# airu-schematic-bb.net
KiCad netlist of a schematic drawn in EAGLE
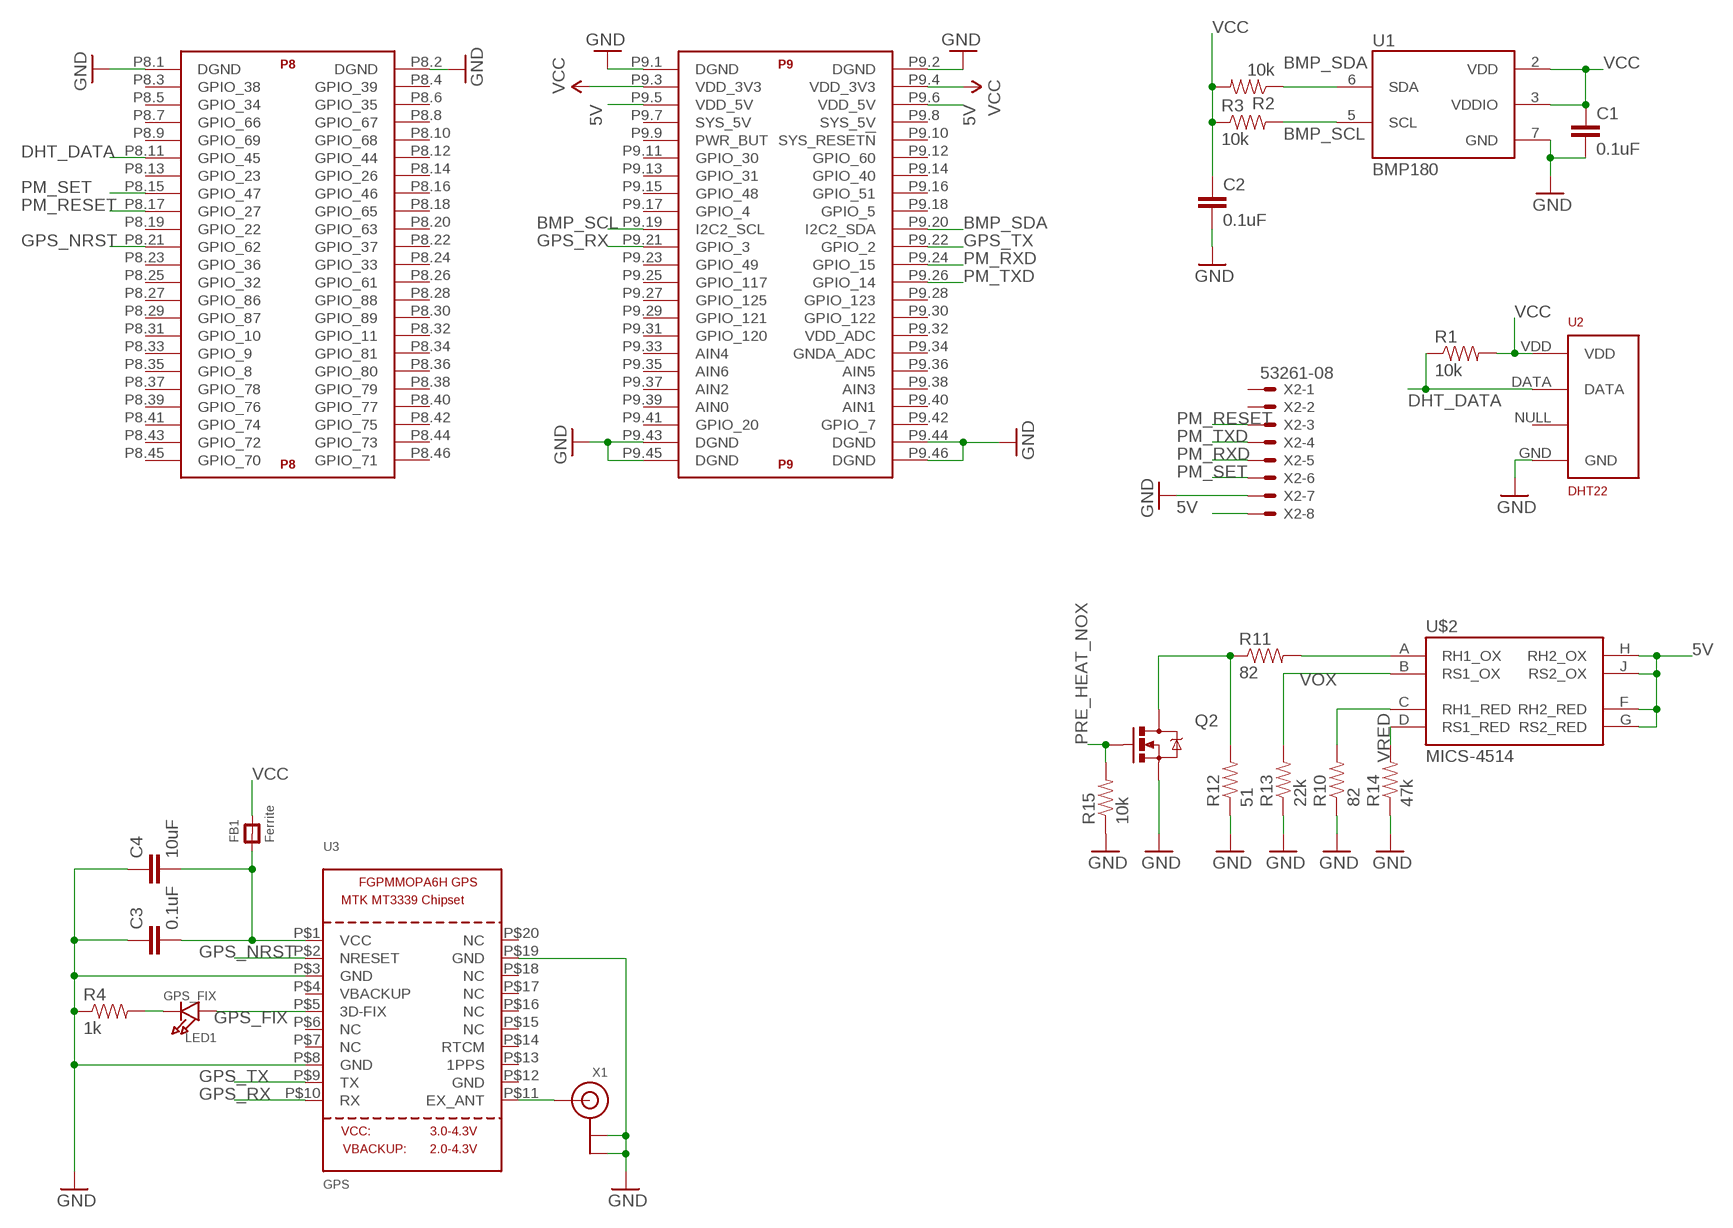
[diagram p0: schematic, sheet 1]

(export (version "E")
  (design (tool "Eeschema 10.0.6"))
  (components
    (comp (ref "C1")
      (value "0.1uF")
      (footprint "eagle-import:1206")
      (libsource (lib "eagle-import") (part "CAP1206"))
    )
    (comp (ref "C2")
      (value "0.1uF")
      (footprint "eagle-import:1206")
      (libsource (lib "eagle-import") (part "CAP1206"))
    )
    (comp (ref "C3")
      (value "0.1uF")
      (footprint "eagle-import:1206")
      (libsource (lib "eagle-import") (part "CAP1206"))
    )
    (comp (ref "C4")
      (value "10uF")
      (footprint "eagle-import:1206")
      (libsource (lib "eagle-import") (part "CAP1206"))
    )
    (comp (ref "FB1")
      (value "Ferrite")
      (footprint "eagle-import:0805")
      (libsource (lib "eagle-import") (part "FERRITE0805"))
    )
    (comp (ref "LED1")
      (value "GPS_FIX")
      (footprint "eagle-import:CHIPLED_1206")
      (libsource (lib "eagle-import") (part "LED1206"))
    )
    (comp (ref "Q2")
      (value "MOSFET-NCHANNELAO3404A")
      (footprint "eagle-import:SOT23-3")
      (libsource (lib "eagle-import") (part "MOSFET-NCHANNELAO3404A"))
    )
    (comp (ref "R1")
      (value "10k")
      (footprint "eagle-import:1206")
      (libsource (lib "eagle-import") (part "RESISTOR1206"))
    )
    (comp (ref "R2")
      (value "10k")
      (footprint "eagle-import:1206")
      (libsource (lib "eagle-import") (part "RESISTOR1206"))
    )
    (comp (ref "R3")
      (value "10k")
      (footprint "eagle-import:1206")
      (libsource (lib "eagle-import") (part "RESISTOR1206"))
    )
    (comp (ref "R4")
      (value "1k")
      (footprint "eagle-import:1206")
      (libsource (lib "eagle-import") (part "RESISTOR1206"))
    )
    (comp (ref "R10")
      (value "82")
      (footprint "eagle-import:1206")
      (libsource (lib "eagle-import") (part "RESISTOR1206"))
    )
    (comp (ref "R11")
      (value "82")
      (footprint "eagle-import:1206")
      (libsource (lib "eagle-import") (part "RESISTOR1206"))
    )
    (comp (ref "R12")
      (value "51")
      (footprint "eagle-import:1206")
      (libsource (lib "eagle-import") (part "RESISTOR1206"))
    )
    (comp (ref "R13")
      (value "22k")
      (footprint "eagle-import:1206")
      (libsource (lib "eagle-import") (part "RESISTOR1206"))
    )
    (comp (ref "R14")
      (value "47k")
      (footprint "eagle-import:1206")
      (libsource (lib "eagle-import") (part "RESISTOR1206"))
    )
    (comp (ref "R15")
      (value "10k")
      (footprint "eagle-import:1206")
      (libsource (lib "eagle-import") (part "RESISTOR1206"))
    )
    (comp (ref "U$1")
      (value "BEAGLE_BONE_BLACK_CAPE")
      (footprint "eagle-import:BEAGLE_BONE_BLACK_CAPE")
      (libsource (lib "eagle-import") (part "BEAGLE_BONE_BLACK_CAPE"))
    )
    (comp (ref "U$2")
      (value "MICS-4514")
      (footprint "eagle-import:MICS_10-SMD")
      (libsource (lib "eagle-import") (part "MICS-4514"))
    )
    (comp (ref "U1")
      (value "BMP180")
      (footprint "eagle-import:BMP180")
      (libsource (lib "eagle-import") (part "BMP180"))
    )
    (comp (ref "U2")
      (value "DHT22")
      (footprint "eagle-import:RHT03_DHT-22")
      (libsource (lib "eagle-import") (part "RHT03_DHT-22_AM2302"))
    )
    (comp (ref "U3")
      (value "GPS")
      (footprint "eagle-import:FGPMMOPA6H")
      (libsource (lib "eagle-import") (part "GPS_FGPMMOPA6H"))
    )
    (comp (ref "X1")
      (value "ANTENNA_U.FL")
      (footprint "eagle-import:U.FL")
      (libsource (lib "eagle-import") (part "ANTENNA_U.FL"))
    )
    (comp (ref "X2")
      (value "53261-08")
      (footprint "eagle-import:53261-08")
      (libsource (lib "eagle-import") (part "53?-08261"))
    )
  )
  (nets
    (net (code "1") (name "/5V") (class "Default")
      (node (ref "U$1") (pin "P9.5") (pinfunction "VDD_5V_P9.5") (pintype "bidirectional"))
      (node (ref "U$1") (pin "P9.6") (pinfunction "VDD_5V_P9.6") (pintype "bidirectional"))
      (node (ref "U$2") (pin "F") (pinfunction "RH2_RED_F") (pintype "bidirectional"))
      (node (ref "U$2") (pin "G") (pinfunction "RS2_RED_G") (pintype "bidirectional"))
      (node (ref "U$2") (pin "H") (pinfunction "RH2_OX_H") (pintype "bidirectional"))
      (node (ref "U$2") (pin "J") (pinfunction "RS2_OX_J") (pintype "bidirectional"))
      (node (ref "X2") (pin "8") (pinfunction "S_8") (pintype "passive"))
    )
    (net (code "2") (name "/BMP_SCL") (class "Default")
      (node (ref "R3") (pin "2") (pinfunction "2_2") (pintype "passive"))
      (node (ref "U$1") (pin "P9.19") (pinfunction "I2C2_SCL_P9.19") (pintype "bidirectional"))
      (node (ref "U1") (pin "5") (pinfunction "SCL_5") (pintype "input"))
    )
    (net (code "3") (name "/BMP_SDA") (class "Default")
      (node (ref "R2") (pin "1") (pinfunction "1_1") (pintype "passive"))
      (node (ref "U$1") (pin "P9.20") (pinfunction "I2C2_SDA_P9.20") (pintype "bidirectional"))
      (node (ref "U1") (pin "6") (pinfunction "SDA_6") (pintype "bidirectional"))
    )
    (net (code "4") (name "/DHT_DATA") (class "Default")
      (node (ref "R1") (pin "1") (pinfunction "1_1") (pintype "passive"))
      (node (ref "U$1") (pin "P8.11") (pinfunction "GPIO_45_P8.11") (pintype "bidirectional"))
      (node (ref "U2") (pin "DATA") (pinfunction "DATA_DATA") (pintype "bidirectional"))
    )
    (net (code "5") (name "/GPS_FIX") (class "Default")
      (node (ref "LED1") (pin "A") (pinfunction "A_A") (pintype "passive"))
      (node (ref "U3") (pin "P$5") (pinfunction "3D-FIX_P$5") (pintype "bidirectional"))
    )
    (net (code "6") (name "/GPS_NRST") (class "Default")
      (node (ref "U$1") (pin "P8.21") (pinfunction "GPIO_62_P8.21") (pintype "bidirectional"))
      (node (ref "U3") (pin "P$2") (pinfunction "NRESET_P$2") (pintype "bidirectional"))
    )
    (net (code "7") (name "/GPS_RX") (class "Default")
      (node (ref "U$1") (pin "P9.21") (pinfunction "GPIO_3_P9.21") (pintype "bidirectional"))
      (node (ref "U3") (pin "P$10") (pinfunction "RX_P$10") (pintype "bidirectional"))
    )
    (net (code "8") (name "/GPS_TX") (class "Default")
      (node (ref "U$1") (pin "P9.22") (pinfunction "GPIO_2_P9.22") (pintype "bidirectional"))
      (node (ref "U3") (pin "P$9") (pinfunction "TX_P$9") (pintype "bidirectional"))
    )
    (net (code "9") (name "/PM_RESET") (class "Default")
      (node (ref "U$1") (pin "P8.17") (pinfunction "GPIO_27_P8.17") (pintype "bidirectional"))
      (node (ref "X2") (pin "3") (pinfunction "S_3") (pintype "passive"))
    )
    (net (code "10") (name "/PM_RXD") (class "Default")
      (node (ref "U$1") (pin "P9.24") (pinfunction "GPIO_15_P9.24") (pintype "bidirectional"))
      (node (ref "X2") (pin "5") (pinfunction "S_5") (pintype "passive"))
    )
    (net (code "11") (name "/PM_SET") (class "Default")
      (node (ref "U$1") (pin "P8.15") (pinfunction "GPIO_47_P8.15") (pintype "bidirectional"))
      (node (ref "X2") (pin "6") (pinfunction "S_6") (pintype "passive"))
    )
    (net (code "12") (name "/PM_TXD") (class "Default")
      (node (ref "U$1") (pin "P9.26") (pinfunction "GPIO_14_P9.26") (pintype "bidirectional"))
      (node (ref "X2") (pin "4") (pinfunction "S_4") (pintype "passive"))
    )
    (net (code "13") (name "/PRE_HEAT_NOX") (class "Default")
      (node (ref "Q2") (pin "1") (pinfunction "G_1") (pintype "passive"))
      (node (ref "R15") (pin "2") (pinfunction "2_2") (pintype "passive"))
    )
    (net (code "14") (name "/VOX") (class "Default")
      (node (ref "R13") (pin "2") (pinfunction "2_2") (pintype "passive"))
      (node (ref "U$2") (pin "B") (pinfunction "RS1_OX_B") (pintype "bidirectional"))
    )
    (net (code "15") (name "/VRED") (class "Default")
      (node (ref "R14") (pin "2") (pinfunction "2_2") (pintype "passive"))
      (node (ref "U$2") (pin "D") (pinfunction "RS1_RED_D") (pintype "bidirectional"))
    )
    (net (code "16") (name "GND") (class "Default")
      (node (ref "C1") (pin "2") (pinfunction "2_2") (pintype "passive"))
      (node (ref "C2") (pin "2") (pinfunction "2_2") (pintype "passive"))
      (node (ref "C3") (pin "1") (pinfunction "1_1") (pintype "passive"))
      (node (ref "C4") (pin "1") (pinfunction "1_1") (pintype "passive"))
      (node (ref "Q2") (pin "2") (pinfunction "S_2") (pintype "passive"))
      (node (ref "R10") (pin "1") (pinfunction "1_1") (pintype "passive"))
      (node (ref "R12") (pin "1") (pinfunction "1_1") (pintype "passive"))
      (node (ref "R13") (pin "1") (pinfunction "1_1") (pintype "passive"))
      (node (ref "R14") (pin "1") (pinfunction "1_1") (pintype "passive"))
      (node (ref "R15") (pin "1") (pinfunction "1_1") (pintype "passive"))
      (node (ref "R4") (pin "1") (pinfunction "1_1") (pintype "passive"))
      (node (ref "U$1") (pin "P8.1") (pinfunction "DGND_P8.1") (pintype "bidirectional"))
      (node (ref "U$1") (pin "P8.2") (pinfunction "DGND_P8.2") (pintype "bidirectional"))
      (node (ref "U$1") (pin "P9.1") (pinfunction "DGND_P9.1") (pintype "bidirectional"))
      (node (ref "U$1") (pin "P9.2") (pinfunction "DGND_P9.2") (pintype "bidirectional"))
      (node (ref "U$1") (pin "P9.43") (pinfunction "DGND_P9.43") (pintype "bidirectional"))
      (node (ref "U$1") (pin "P9.44") (pinfunction "DGND_P9.44") (pintype "bidirectional"))
      (node (ref "U$1") (pin "P9.45") (pinfunction "DGND_P9.45") (pintype "bidirectional"))
      (node (ref "U$1") (pin "P9.46") (pinfunction "DGND_P9.46") (pintype "bidirectional"))
      (node (ref "U1") (pin "7") (pinfunction "GND_7") (pintype "power_in"))
      (node (ref "U2") (pin "GND") (pinfunction "GND_GND") (pintype "power_in"))
      (node (ref "U3") (pin "P$19") (pinfunction "GND_P$19") (pintype "bidirectional"))
      (node (ref "U3") (pin "P$3") (pinfunction "GND_P$3") (pintype "bidirectional"))
      (node (ref "U3") (pin "P$8") (pinfunction "GND_P$8") (pintype "bidirectional"))
      (node (ref "X1") (pin "1") (pinfunction "GND_1") (pintype "passive"))
      (node (ref "X1") (pin "2") (pinfunction "GND_2") (pintype "passive"))
      (node (ref "X2") (pin "7") (pinfunction "S_7") (pintype "passive"))
    )
    (net (code "17") (name "Net-(FB1-P$1)") (class "Default")
      (node (ref "C3") (pin "2") (pinfunction "2_2") (pintype "passive"))
      (node (ref "C4") (pin "2") (pinfunction "2_2") (pintype "passive"))
      (node (ref "FB1") (pin "1") (pinfunction "P$1_1") (pintype "passive"))
      (node (ref "U3") (pin "P$1") (pinfunction "VCC_P$1") (pintype "bidirectional"))
    )
    (net (code "18") (name "Net-(LED1-PadC)") (class "Default")
      (node (ref "LED1") (pin "C") (pinfunction "C_C") (pintype "passive"))
      (node (ref "R4") (pin "2") (pinfunction "2_2") (pintype "passive"))
    )
    (net (code "19") (name "Net-(Q2-D)") (class "Default")
      (node (ref "Q2") (pin "3") (pinfunction "D_3") (pintype "passive"))
      (node (ref "R11") (pin "1") (pinfunction "1_1") (pintype "passive"))
      (node (ref "R12") (pin "2") (pinfunction "2_2") (pintype "passive"))
    )
    (net (code "20") (name "Net-(U$2-RH1_OX)") (class "Default")
      (node (ref "R11") (pin "2") (pinfunction "2_2") (pintype "passive"))
      (node (ref "U$2") (pin "A") (pinfunction "RH1_OX_A") (pintype "bidirectional"))
    )
    (net (code "21") (name "Net-(U$2-RH1_RED)") (class "Default")
      (node (ref "R10") (pin "2") (pinfunction "2_2") (pintype "passive"))
      (node (ref "U$2") (pin "C") (pinfunction "RH1_RED_C") (pintype "bidirectional"))
    )
    (net (code "22") (name "Net-(U3-EX_ANT)") (class "Default")
      (node (ref "U3") (pin "P$11") (pinfunction "EX_ANT_P$11") (pintype "bidirectional"))
      (node (ref "X1") (pin "3") (pinfunction "SIGNAL_3") (pintype "passive"))
    )
    (net (code "23") (name "VCC") (class "Default")
      (node (ref "C1") (pin "1") (pinfunction "1_1") (pintype "passive"))
      (node (ref "C2") (pin "1") (pinfunction "1_1") (pintype "passive"))
      (node (ref "FB1") (pin "2") (pinfunction "P$2_2") (pintype "passive"))
      (node (ref "R1") (pin "2") (pinfunction "2_2") (pintype "passive"))
      (node (ref "R2") (pin "2") (pinfunction "2_2") (pintype "passive"))
      (node (ref "R3") (pin "1") (pinfunction "1_1") (pintype "passive"))
      (node (ref "U$1") (pin "P9.3") (pinfunction "VDD_3V3_P9.3") (pintype "bidirectional"))
      (node (ref "U$1") (pin "P9.4") (pinfunction "VDD_3V3_P9.4") (pintype "bidirectional"))
      (node (ref "U1") (pin "2") (pinfunction "VDD_2") (pintype "power_in"))
      (node (ref "U1") (pin "3") (pinfunction "VDDIO_3") (pintype "power_in"))
      (node (ref "U2") (pin "VDD") (pinfunction "VDD_VDD") (pintype "power_in"))
    )
    (net (code "24") (name "unconnected-(U$1A-GPIO_8-PadP8.35)") (class "Default")
      (node (ref "U$1") (pin "P8.35") (pinfunction "GPIO_8_P8.35") (pintype "bidirectional"))
    )
    (net (code "25") (name "unconnected-(U$1A-GPIO_9-PadP8.33)") (class "Default")
      (node (ref "U$1") (pin "P8.33") (pinfunction "GPIO_9_P8.33") (pintype "bidirectional"))
    )
    (net (code "26") (name "unconnected-(U$1A-GPIO_10-PadP8.31)") (class "Default")
      (node (ref "U$1") (pin "P8.31") (pinfunction "GPIO_10_P8.31") (pintype "bidirectional"))
    )
    (net (code "27") (name "unconnected-(U$1A-GPIO_11-PadP8.32)") (class "Default")
      (node (ref "U$1") (pin "P8.32") (pinfunction "GPIO_11_P8.32") (pintype "bidirectional"))
    )
    (net (code "28") (name "unconnected-(U$1A-GPIO_22-PadP8.19)") (class "Default")
      (node (ref "U$1") (pin "P8.19") (pinfunction "GPIO_22_P8.19") (pintype "bidirectional"))
    )
    (net (code "29") (name "unconnected-(U$1A-GPIO_23-PadP8.13)") (class "Default")
      (node (ref "U$1") (pin "P8.13") (pinfunction "GPIO_23_P8.13") (pintype "bidirectional"))
    )
    (net (code "30") (name "unconnected-(U$1A-GPIO_26-PadP8.14)") (class "Default")
      (node (ref "U$1") (pin "P8.14") (pinfunction "GPIO_26_P8.14") (pintype "bidirectional"))
    )
    (net (code "31") (name "unconnected-(U$1A-GPIO_32-PadP8.25)") (class "Default")
      (node (ref "U$1") (pin "P8.25") (pinfunction "GPIO_32_P8.25") (pintype "bidirectional"))
    )
    (net (code "32") (name "unconnected-(U$1A-GPIO_33-PadP8.24)") (class "Default")
      (node (ref "U$1") (pin "P8.24") (pinfunction "GPIO_33_P8.24") (pintype "bidirectional"))
    )
    (net (code "33") (name "unconnected-(U$1A-GPIO_34-PadP8.5)") (class "Default")
      (node (ref "U$1") (pin "P8.5") (pinfunction "GPIO_34_P8.5") (pintype "bidirectional"))
    )
    (net (code "34") (name "unconnected-(U$1A-GPIO_35-PadP8.6)") (class "Default")
      (node (ref "U$1") (pin "P8.6") (pinfunction "GPIO_35_P8.6") (pintype "bidirectional"))
    )
    (net (code "35") (name "unconnected-(U$1A-GPIO_36-PadP8.23)") (class "Default")
      (node (ref "U$1") (pin "P8.23") (pinfunction "GPIO_36_P8.23") (pintype "bidirectional"))
    )
    (net (code "36") (name "unconnected-(U$1A-GPIO_37-PadP8.22)") (class "Default")
      (node (ref "U$1") (pin "P8.22") (pinfunction "GPIO_37_P8.22") (pintype "bidirectional"))
    )
    (net (code "37") (name "unconnected-(U$1A-GPIO_38-PadP8.3)") (class "Default")
      (node (ref "U$1") (pin "P8.3") (pinfunction "GPIO_38_P8.3") (pintype "bidirectional"))
    )
    (net (code "38") (name "unconnected-(U$1A-GPIO_39-PadP8.4)") (class "Default")
      (node (ref "U$1") (pin "P8.4") (pinfunction "GPIO_39_P8.4") (pintype "bidirectional"))
    )
    (net (code "39") (name "unconnected-(U$1A-GPIO_44-PadP8.12)") (class "Default")
      (node (ref "U$1") (pin "P8.12") (pinfunction "GPIO_44_P8.12") (pintype "bidirectional"))
    )
    (net (code "40") (name "unconnected-(U$1A-GPIO_46-PadP8.16)") (class "Default")
      (node (ref "U$1") (pin "P8.16") (pinfunction "GPIO_46_P8.16") (pintype "bidirectional"))
    )
    (net (code "41") (name "unconnected-(U$1A-GPIO_61-PadP8.26)") (class "Default")
      (node (ref "U$1") (pin "P8.26") (pinfunction "GPIO_61_P8.26") (pintype "bidirectional"))
    )
    (net (code "42") (name "unconnected-(U$1A-GPIO_63-PadP8.20)") (class "Default")
      (node (ref "U$1") (pin "P8.20") (pinfunction "GPIO_63_P8.20") (pintype "bidirectional"))
    )
    (net (code "43") (name "unconnected-(U$1A-GPIO_65-PadP8.18)") (class "Default")
      (node (ref "U$1") (pin "P8.18") (pinfunction "GPIO_65_P8.18") (pintype "bidirectional"))
    )
    (net (code "44") (name "unconnected-(U$1A-GPIO_66-PadP8.7)") (class "Default")
      (node (ref "U$1") (pin "P8.7") (pinfunction "GPIO_66_P8.7") (pintype "bidirectional"))
    )
    (net (code "45") (name "unconnected-(U$1A-GPIO_67-PadP8.8)") (class "Default")
      (node (ref "U$1") (pin "P8.8") (pinfunction "GPIO_67_P8.8") (pintype "bidirectional"))
    )
    (net (code "46") (name "unconnected-(U$1A-GPIO_68-PadP8.10)") (class "Default")
      (node (ref "U$1") (pin "P8.10") (pinfunction "GPIO_68_P8.10") (pintype "bidirectional"))
    )
    (net (code "47") (name "unconnected-(U$1A-GPIO_69-PadP8.9)") (class "Default")
      (node (ref "U$1") (pin "P8.9") (pinfunction "GPIO_69_P8.9") (pintype "bidirectional"))
    )
    (net (code "48") (name "unconnected-(U$1A-GPIO_70-PadP8.45)") (class "Default")
      (node (ref "U$1") (pin "P8.45") (pinfunction "GPIO_70_P8.45") (pintype "bidirectional"))
    )
    (net (code "49") (name "unconnected-(U$1A-GPIO_71-PadP8.46)") (class "Default")
      (node (ref "U$1") (pin "P8.46") (pinfunction "GPIO_71_P8.46") (pintype "bidirectional"))
    )
    (net (code "50") (name "unconnected-(U$1A-GPIO_72-PadP8.43)") (class "Default")
      (node (ref "U$1") (pin "P8.43") (pinfunction "GPIO_72_P8.43") (pintype "bidirectional"))
    )
    (net (code "51") (name "unconnected-(U$1A-GPIO_73-PadP8.44)") (class "Default")
      (node (ref "U$1") (pin "P8.44") (pinfunction "GPIO_73_P8.44") (pintype "bidirectional"))
    )
    (net (code "52") (name "unconnected-(U$1A-GPIO_74-PadP8.41)") (class "Default")
      (node (ref "U$1") (pin "P8.41") (pinfunction "GPIO_74_P8.41") (pintype "bidirectional"))
    )
    (net (code "53") (name "unconnected-(U$1A-GPIO_75-PadP8.42)") (class "Default")
      (node (ref "U$1") (pin "P8.42") (pinfunction "GPIO_75_P8.42") (pintype "bidirectional"))
    )
    (net (code "54") (name "unconnected-(U$1A-GPIO_76-PadP8.39)") (class "Default")
      (node (ref "U$1") (pin "P8.39") (pinfunction "GPIO_76_P8.39") (pintype "bidirectional"))
    )
    (net (code "55") (name "unconnected-(U$1A-GPIO_77-PadP8.40)") (class "Default")
      (node (ref "U$1") (pin "P8.40") (pinfunction "GPIO_77_P8.40") (pintype "bidirectional"))
    )
    (net (code "56") (name "unconnected-(U$1A-GPIO_78-PadP8.37)") (class "Default")
      (node (ref "U$1") (pin "P8.37") (pinfunction "GPIO_78_P8.37") (pintype "bidirectional"))
    )
    (net (code "57") (name "unconnected-(U$1A-GPIO_79-PadP8.38)") (class "Default")
      (node (ref "U$1") (pin "P8.38") (pinfunction "GPIO_79_P8.38") (pintype "bidirectional"))
    )
    (net (code "58") (name "unconnected-(U$1A-GPIO_80-PadP8.36)") (class "Default")
      (node (ref "U$1") (pin "P8.36") (pinfunction "GPIO_80_P8.36") (pintype "bidirectional"))
    )
    (net (code "59") (name "unconnected-(U$1A-GPIO_81-PadP8.34)") (class "Default")
      (node (ref "U$1") (pin "P8.34") (pinfunction "GPIO_81_P8.34") (pintype "bidirectional"))
    )
    (net (code "60") (name "unconnected-(U$1A-GPIO_86-PadP8.27)") (class "Default")
      (node (ref "U$1") (pin "P8.27") (pinfunction "GPIO_86_P8.27") (pintype "bidirectional"))
    )
    (net (code "61") (name "unconnected-(U$1A-GPIO_87-PadP8.29)") (class "Default")
      (node (ref "U$1") (pin "P8.29") (pinfunction "GPIO_87_P8.29") (pintype "bidirectional"))
    )
    (net (code "62") (name "unconnected-(U$1A-GPIO_88-PadP8.28)") (class "Default")
      (node (ref "U$1") (pin "P8.28") (pinfunction "GPIO_88_P8.28") (pintype "bidirectional"))
    )
    (net (code "63") (name "unconnected-(U$1A-GPIO_89-PadP8.30)") (class "Default")
      (node (ref "U$1") (pin "P8.30") (pinfunction "GPIO_89_P8.30") (pintype "bidirectional"))
    )
    (net (code "64") (name "unconnected-(U$1B-AIN0-PadP9.39)") (class "Default")
      (node (ref "U$1") (pin "P9.39") (pinfunction "AIN0_P9.39") (pintype "bidirectional"))
    )
    (net (code "65") (name "unconnected-(U$1B-AIN1-PadP9.40)") (class "Default")
      (node (ref "U$1") (pin "P9.40") (pinfunction "AIN1_P9.40") (pintype "bidirectional"))
    )
    (net (code "66") (name "unconnected-(U$1B-AIN2-PadP9.37)") (class "Default")
      (node (ref "U$1") (pin "P9.37") (pinfunction "AIN2_P9.37") (pintype "bidirectional"))
    )
    (net (code "67") (name "unconnected-(U$1B-AIN3-PadP9.38)") (class "Default")
      (node (ref "U$1") (pin "P9.38") (pinfunction "AIN3_P9.38") (pintype "bidirectional"))
    )
    (net (code "68") (name "unconnected-(U$1B-AIN4-PadP9.33)") (class "Default")
      (node (ref "U$1") (pin "P9.33") (pinfunction "AIN4_P9.33") (pintype "bidirectional"))
    )
    (net (code "69") (name "unconnected-(U$1B-AIN5-PadP9.36)") (class "Default")
      (node (ref "U$1") (pin "P9.36") (pinfunction "AIN5_P9.36") (pintype "bidirectional"))
    )
    (net (code "70") (name "unconnected-(U$1B-AIN6-PadP9.35)") (class "Default")
      (node (ref "U$1") (pin "P9.35") (pinfunction "AIN6_P9.35") (pintype "bidirectional"))
    )
    (net (code "71") (name "unconnected-(U$1B-GNDA_ADC-PadP9.34)") (class "Default")
      (node (ref "U$1") (pin "P9.34") (pinfunction "GNDA_ADC_P9.34") (pintype "bidirectional"))
    )
    (net (code "72") (name "unconnected-(U$1B-GPIO_4-PadP9.17)") (class "Default")
      (node (ref "U$1") (pin "P9.17") (pinfunction "GPIO_4_P9.17") (pintype "bidirectional"))
    )
    (net (code "73") (name "unconnected-(U$1B-GPIO_5-PadP9.18)") (class "Default")
      (node (ref "U$1") (pin "P9.18") (pinfunction "GPIO_5_P9.18") (pintype "bidirectional"))
    )
    (net (code "74") (name "unconnected-(U$1B-GPIO_7-PadP9.42)") (class "Default")
      (node (ref "U$1") (pin "P9.42") (pinfunction "GPIO_7_P9.42") (pintype "bidirectional"))
    )
    (net (code "75") (name "unconnected-(U$1B-GPIO_20-PadP9.41)") (class "Default")
      (node (ref "U$1") (pin "P9.41") (pinfunction "GPIO_20_P9.41") (pintype "bidirectional"))
    )
    (net (code "76") (name "unconnected-(U$1B-GPIO_30-PadP9.11)") (class "Default")
      (node (ref "U$1") (pin "P9.11") (pinfunction "GPIO_30_P9.11") (pintype "bidirectional"))
    )
    (net (code "77") (name "unconnected-(U$1B-GPIO_31-PadP9.13)") (class "Default")
      (node (ref "U$1") (pin "P9.13") (pinfunction "GPIO_31_P9.13") (pintype "bidirectional"))
    )
    (net (code "78") (name "unconnected-(U$1B-GPIO_40-PadP9.14)") (class "Default")
      (node (ref "U$1") (pin "P9.14") (pinfunction "GPIO_40_P9.14") (pintype "bidirectional"))
    )
    (net (code "79") (name "unconnected-(U$1B-GPIO_48-PadP9.15)") (class "Default")
      (node (ref "U$1") (pin "P9.15") (pinfunction "GPIO_48_P9.15") (pintype "bidirectional"))
    )
    (net (code "80") (name "unconnected-(U$1B-GPIO_49-PadP9.23)") (class "Default")
      (node (ref "U$1") (pin "P9.23") (pinfunction "GPIO_49_P9.23") (pintype "bidirectional"))
    )
    (net (code "81") (name "unconnected-(U$1B-GPIO_51-PadP9.16)") (class "Default")
      (node (ref "U$1") (pin "P9.16") (pinfunction "GPIO_51_P9.16") (pintype "bidirectional"))
    )
    (net (code "82") (name "unconnected-(U$1B-GPIO_60-PadP9.12)") (class "Default")
      (node (ref "U$1") (pin "P9.12") (pinfunction "GPIO_60_P9.12") (pintype "bidirectional"))
    )
    (net (code "83") (name "unconnected-(U$1B-GPIO_117-PadP9.25)") (class "Default")
      (node (ref "U$1") (pin "P9.25") (pinfunction "GPIO_117_P9.25") (pintype "bidirectional"))
    )
    (net (code "84") (name "unconnected-(U$1B-GPIO_120-PadP9.31)") (class "Default")
      (node (ref "U$1") (pin "P9.31") (pinfunction "GPIO_120_P9.31") (pintype "bidirectional"))
    )
    (net (code "85") (name "unconnected-(U$1B-GPIO_121-PadP9.29)") (class "Default")
      (node (ref "U$1") (pin "P9.29") (pinfunction "GPIO_121_P9.29") (pintype "bidirectional"))
    )
    (net (code "86") (name "unconnected-(U$1B-GPIO_122-PadP9.30)") (class "Default")
      (node (ref "U$1") (pin "P9.30") (pinfunction "GPIO_122_P9.30") (pintype "bidirectional"))
    )
    (net (code "87") (name "unconnected-(U$1B-GPIO_123-PadP9.28)") (class "Default")
      (node (ref "U$1") (pin "P9.28") (pinfunction "GPIO_123_P9.28") (pintype "bidirectional"))
    )
    (net (code "88") (name "unconnected-(U$1B-GPIO_125-PadP9.27)") (class "Default")
      (node (ref "U$1") (pin "P9.27") (pinfunction "GPIO_125_P9.27") (pintype "bidirectional"))
    )
    (net (code "89") (name "unconnected-(U$1B-PWR_BUT-PadP9.9)") (class "Default")
      (node (ref "U$1") (pin "P9.9") (pinfunction "PWR_BUT_P9.9") (pintype "bidirectional"))
    )
    (net (code "90") (name "unconnected-(U$1B-SYS_5V-PadP9.7)") (class "Default")
      (node (ref "U$1") (pin "P9.7") (pinfunction "SYS_5V_P9.7") (pintype "bidirectional"))
    )
    (net (code "91") (name "unconnected-(U$1B-SYS_5V-PadP9.8)") (class "Default")
      (node (ref "U$1") (pin "P9.8") (pinfunction "SYS_5V_P9.8") (pintype "bidirectional"))
    )
    (net (code "92") (name "unconnected-(U$1B-SYS_RESET~{N}-PadP9.10)") (class "Default")
      (node (ref "U$1") (pin "P9.10") (pinfunction "SYS_RESET~{N}_P9.10") (pintype "bidirectional"))
    )
    (net (code "93") (name "unconnected-(U$1B-VDD_ADC-PadP9.32)") (class "Default")
      (node (ref "U$1") (pin "P9.32") (pinfunction "VDD_ADC_P9.32") (pintype "bidirectional"))
    )
    (net (code "94") (name "unconnected-(U2-PadNULL)") (class "Default")
      (node (ref "U2") (pin "NULL") (pinfunction "NULL_NULL") (pintype "no_connect"))
    )
    (net (code "95") (name "unconnected-(U3-1PPS-PadP$13)") (class "Default")
      (node (ref "U3") (pin "P$13") (pinfunction "1PPS_P$13") (pintype "bidirectional"))
    )
    (net (code "96") (name "unconnected-(U3-GND-PadP$12)") (class "Default")
      (node (ref "U3") (pin "P$12") (pinfunction "GND_P$12") (pintype "bidirectional"))
    )
    (net (code "97") (name "unconnected-(U3-NC-PadP$6)") (class "Default")
      (node (ref "U3") (pin "P$6") (pinfunction "NC_P$6") (pintype "bidirectional"))
    )
    (net (code "98") (name "unconnected-(U3-NC-PadP$7)") (class "Default")
      (node (ref "U3") (pin "P$7") (pinfunction "NC_P$7") (pintype "bidirectional"))
    )
    (net (code "99") (name "unconnected-(U3-NC-PadP$15)") (class "Default")
      (node (ref "U3") (pin "P$15") (pinfunction "NC_P$15") (pintype "bidirectional"))
    )
    (net (code "100") (name "unconnected-(U3-NC-PadP$16)") (class "Default")
      (node (ref "U3") (pin "P$16") (pinfunction "NC_P$16") (pintype "bidirectional"))
    )
    (net (code "101") (name "unconnected-(U3-NC-PadP$17)") (class "Default")
      (node (ref "U3") (pin "P$17") (pinfunction "NC_P$17") (pintype "bidirectional"))
    )
    (net (code "102") (name "unconnected-(U3-NC-PadP$18)") (class "Default")
      (node (ref "U3") (pin "P$18") (pinfunction "NC_P$18") (pintype "bidirectional"))
    )
    (net (code "103") (name "unconnected-(U3-NC-PadP$20)") (class "Default")
      (node (ref "U3") (pin "P$20") (pinfunction "NC_P$20") (pintype "bidirectional"))
    )
    (net (code "104") (name "unconnected-(U3-RTCM-PadP$14)") (class "Default")
      (node (ref "U3") (pin "P$14") (pinfunction "RTCM_P$14") (pintype "bidirectional"))
    )
    (net (code "105") (name "unconnected-(U3-VBACKUP-PadP$4)") (class "Default")
      (node (ref "U3") (pin "P$4") (pinfunction "VBACKUP_P$4") (pintype "bidirectional"))
    )
    (net (code "106") (name "unconnected-(X2A-S-Pad1)") (class "Default")
      (node (ref "X2") (pin "1") (pinfunction "S_1") (pintype "passive"))
    )
    (net (code "107") (name "unconnected-(X2B-S-Pad2)") (class "Default")
      (node (ref "X2") (pin "2") (pinfunction "S_2") (pintype "passive"))
    )
  )
)
